# SignalMast-ColorLight-DualHead.net
KiCad netlist of a schematic drawn in EAGLE
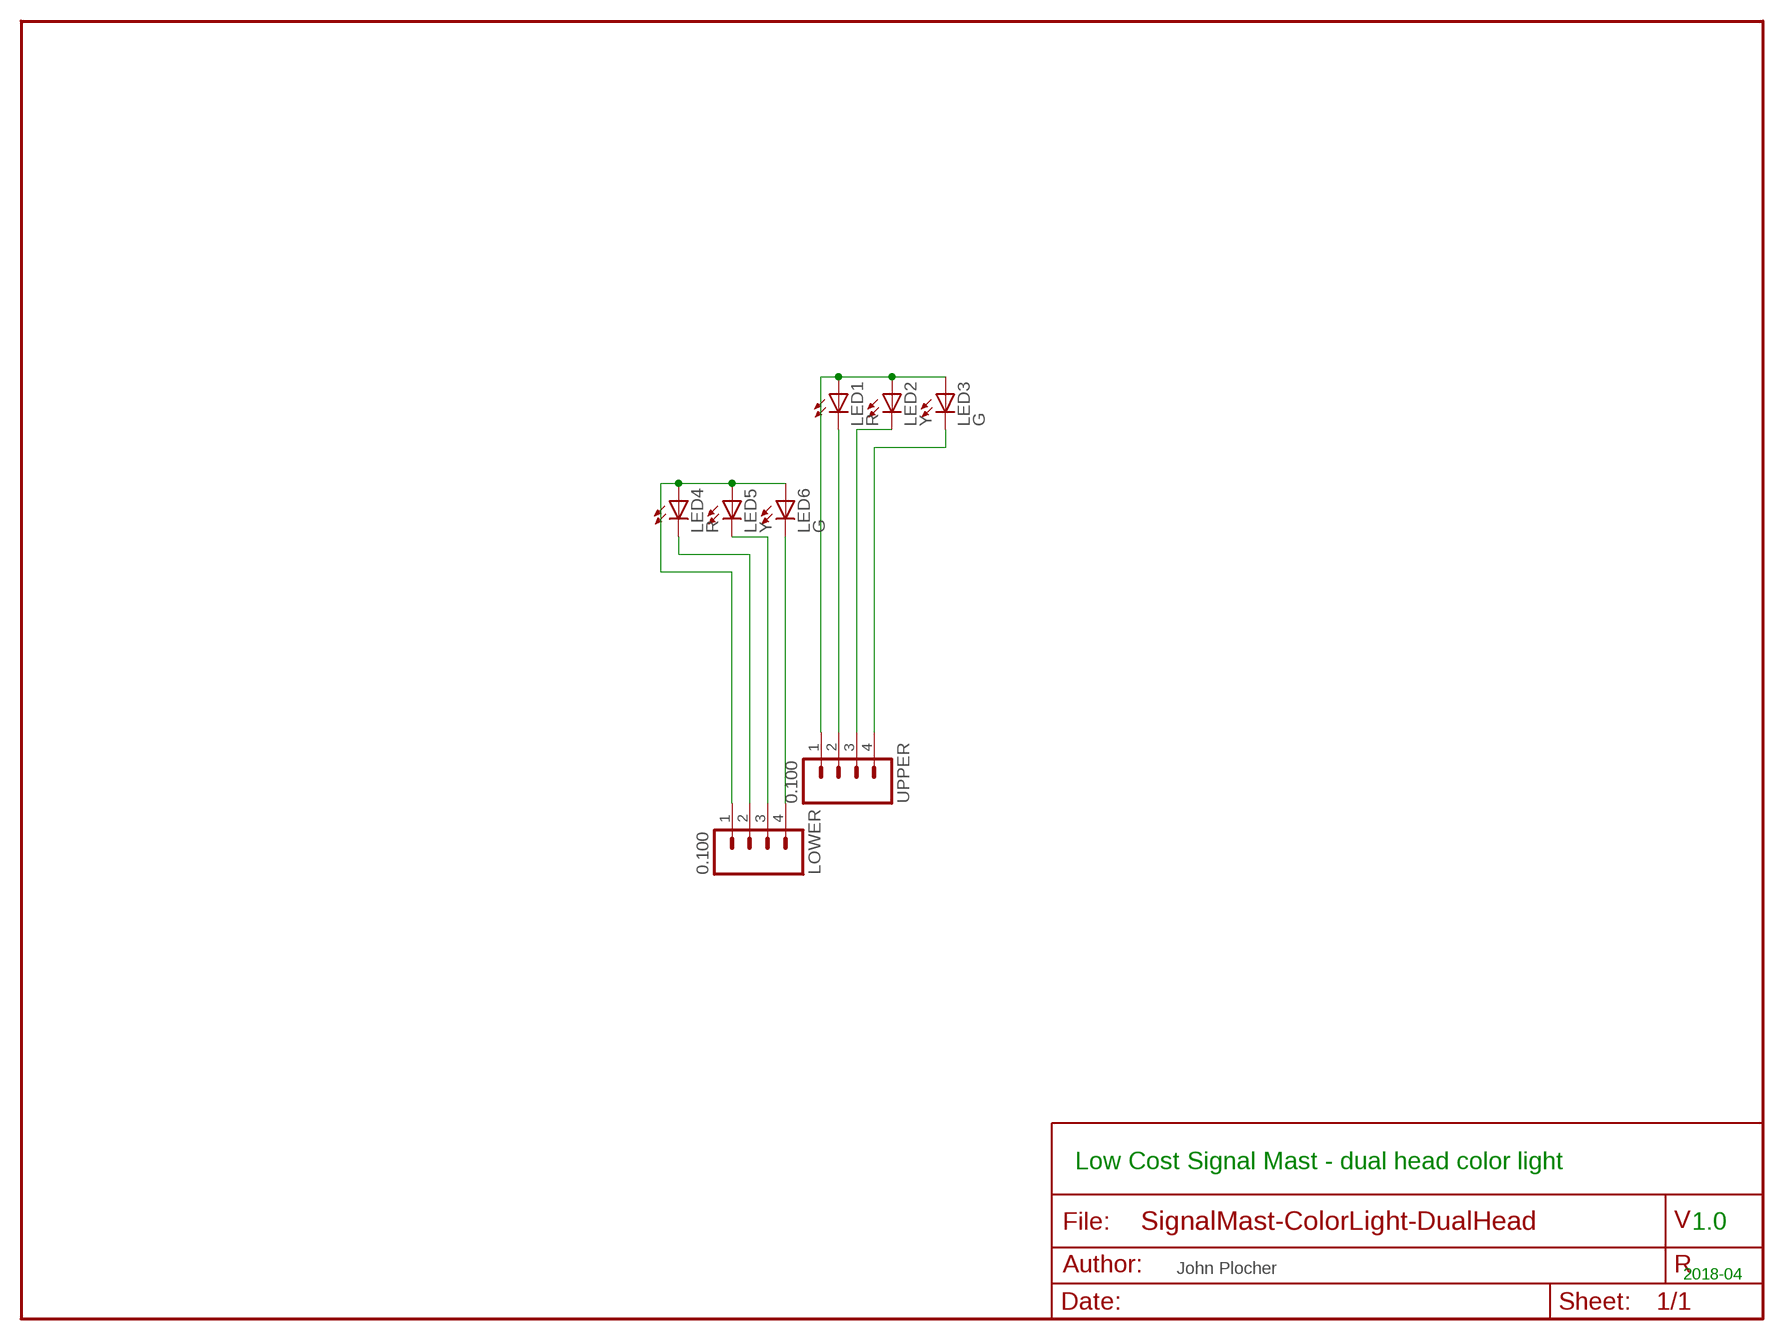
[diagram p0: schematic, sheet 1]

(export (version "E")
  (design (tool "Eeschema 10.0.6"))
  (components
    (comp (ref "LED1")
      (value "R")
      (footprint "eagle-import:0603-LED")
      (libsource (lib "eagle-import") (part "LED0603-LED"))
    )
    (comp (ref "LED2")
      (value "Y")
      (footprint "eagle-import:0603-LED")
      (libsource (lib "eagle-import") (part "LED0603-LED"))
    )
    (comp (ref "LED3")
      (value "G")
      (footprint "eagle-import:0603-LED")
      (libsource (lib "eagle-import") (part "LED0603-LED"))
    )
    (comp (ref "LED4")
      (value "R")
      (footprint "eagle-import:0603-LED")
      (libsource (lib "eagle-import") (part "LED0603-LED"))
    )
    (comp (ref "LED5")
      (value "Y")
      (footprint "eagle-import:0603-LED")
      (libsource (lib "eagle-import") (part "LED0603-LED"))
    )
    (comp (ref "LED6")
      (value "G")
      (footprint "eagle-import:0603-LED")
      (libsource (lib "eagle-import") (part "LED0603-LED"))
    )
    (comp (ref "LOWER")
      (value "0.100")
      (footprint "eagle-import:1X04_LOCK")
      (libsource (lib "eagle-import") (part "CONNECTOR-M04LOCK"))
    )
    (comp (ref "UPPER")
      (value "0.100")
      (footprint "eagle-import:1X04_LOCK")
      (libsource (lib "eagle-import") (part "CONNECTOR-M04LOCK"))
    )
  )
  (nets
    (net (code "1") (name "Net-(LED1-PadA)") (class "Default")
      (node (ref "LED1") (pin "A") (pinfunction "A_A") (pintype "passive"))
      (node (ref "LED2") (pin "A") (pinfunction "A_A") (pintype "passive"))
      (node (ref "LED3") (pin "A") (pinfunction "A_A") (pintype "passive"))
      (node (ref "UPPER") (pin "1") (pinfunction "1_1") (pintype "passive"))
    )
    (net (code "2") (name "Net-(LED1-PadC)") (class "Default")
      (node (ref "LED1") (pin "C") (pinfunction "C_C") (pintype "passive"))
      (node (ref "UPPER") (pin "2") (pinfunction "2_2") (pintype "passive"))
    )
    (net (code "3") (name "Net-(LED2-PadC)") (class "Default")
      (node (ref "LED2") (pin "C") (pinfunction "C_C") (pintype "passive"))
      (node (ref "UPPER") (pin "3") (pinfunction "3_3") (pintype "passive"))
    )
    (net (code "4") (name "Net-(LED3-PadC)") (class "Default")
      (node (ref "LED3") (pin "C") (pinfunction "C_C") (pintype "passive"))
      (node (ref "UPPER") (pin "4") (pinfunction "4_4") (pintype "passive"))
    )
    (net (code "5") (name "Net-(LED4-PadA)") (class "Default")
      (node (ref "LED4") (pin "A") (pinfunction "A_A") (pintype "passive"))
      (node (ref "LED5") (pin "A") (pinfunction "A_A") (pintype "passive"))
      (node (ref "LED6") (pin "A") (pinfunction "A_A") (pintype "passive"))
      (node (ref "LOWER") (pin "1") (pinfunction "1_1") (pintype "passive"))
    )
    (net (code "6") (name "Net-(LED4-PadC)") (class "Default")
      (node (ref "LED4") (pin "C") (pinfunction "C_C") (pintype "passive"))
      (node (ref "LOWER") (pin "2") (pinfunction "2_2") (pintype "passive"))
    )
    (net (code "7") (name "Net-(LED5-PadC)") (class "Default")
      (node (ref "LED5") (pin "C") (pinfunction "C_C") (pintype "passive"))
      (node (ref "LOWER") (pin "3") (pinfunction "3_3") (pintype "passive"))
    )
    (net (code "8") (name "Net-(LED6-PadC)") (class "Default")
      (node (ref "LED6") (pin "C") (pinfunction "C_C") (pintype "passive"))
      (node (ref "LOWER") (pin "4") (pinfunction "4_4") (pintype "passive"))
    )
  )
)
